# MCU.net
KiCad netlist of a schematic drawn in Altium Designer
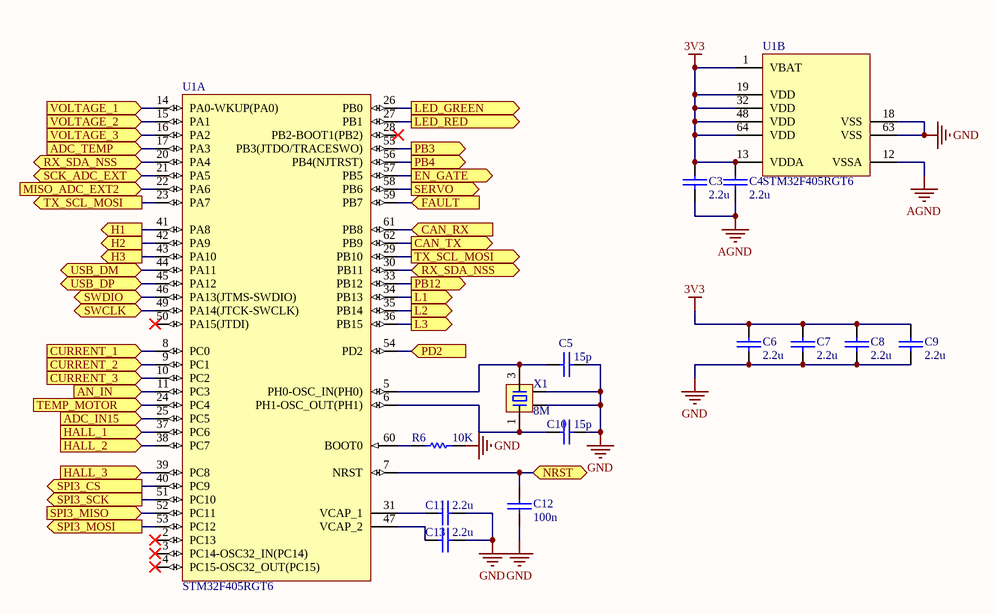
[diagram p0: MCU.SchDoc]

(export (version "E")
  (design (tool "Eeschema 10.0.6"))
  (components
    (comp (ref "C3")
      (value "2.2u")
      (footprint "0603C")
      (description "无极性电容")
      (libsource (lib "电容") (part "CAP"))
    )
    (comp (ref "C4")
      (value "2.2u")
      (footprint "0603C")
      (description "无极性电容")
      (libsource (lib "电容") (part "CAP"))
    )
    (comp (ref "C5")
      (value "15p")
      (footprint "0603C")
      (description "无极性电容")
      (libsource (lib "电容") (part "CAP"))
    )
    (comp (ref "C6")
      (value "2.2u")
      (footprint "0603C")
      (description "无极性电容")
      (libsource (lib "电容") (part "CAP"))
    )
    (comp (ref "C7")
      (value "2.2u")
      (footprint "0603C")
      (description "无极性电容")
      (libsource (lib "电容") (part "CAP"))
    )
    (comp (ref "C8")
      (value "2.2u")
      (footprint "0603C")
      (description "无极性电容")
      (libsource (lib "电容") (part "CAP"))
    )
    (comp (ref "C9")
      (value "2.2u")
      (footprint "0603C")
      (description "无极性电容")
      (libsource (lib "电容") (part "CAP"))
    )
    (comp (ref "C10")
      (value "15p")
      (footprint "0603C")
      (description "无极性电容")
      (libsource (lib "电容") (part "CAP"))
    )
    (comp (ref "C11")
      (value "2.2u")
      (footprint "0603C")
      (description "无极性电容")
      (libsource (lib "电容") (part "CAP"))
    )
    (comp (ref "C12")
      (value "100n")
      (footprint "0603C")
      (description "无极性电容")
      (libsource (lib "电容") (part "CAP"))
    )
    (comp (ref "C13")
      (value "2.2u")
      (footprint "0603C")
      (description "无极性电容")
      (libsource (lib "电容") (part "CAP"))
    )
    (comp (ref "R6") (value "10K") (footprint "0603R") (libsource (lib "电阻") (part "RES")))
    (comp (ref "U1")
      (value "STM32F405RGT6")
      (footprint "STM-LQFP64_N")
      (fields (field (name "MANUFACTURER") "STMicroelectronics"))
      (libsource (lib "Altium Content Vault") (part "MC-ARM-STM32F4X5-SQ64"))
    )
    (comp (ref "X1")
      (value "8M")
      (footprint "OSC 5032-4P")
      (description "4脚无源晶振")
      (libsource (lib "晶振") (part "XTAL-4P"))
    )
  )
  (nets
    (net (code "1") (name "/ADC_IN15") (class "Default")
      (node (ref "U1") (pin "25") (pinfunction "PC5_25") (pintype "bidirectional"))
    )
    (net (code "2") (name "/ADC_TEMP") (class "Default")
      (node (ref "U1") (pin "17") (pinfunction "PA3_17") (pintype "bidirectional"))
    )
    (net (code "3") (name "/AN_IN") (class "Default")
      (node (ref "U1") (pin "11") (pinfunction "PC3_11") (pintype "bidirectional"))
    )
    (net (code "4") (name "/CAN_RX") (class "Default")
      (node (ref "U1") (pin "61") (pinfunction "PB8_61") (pintype "bidirectional"))
    )
    (net (code "5") (name "/CAN_TX") (class "Default")
      (node (ref "U1") (pin "62") (pinfunction "PB9_62") (pintype "bidirectional"))
    )
    (net (code "6") (name "/CURRENT_1") (class "Default")
      (node (ref "U1") (pin "8") (pinfunction "PC0_8") (pintype "bidirectional"))
    )
    (net (code "7") (name "/CURRENT_2") (class "Default")
      (node (ref "U1") (pin "9") (pinfunction "PC1_9") (pintype "bidirectional"))
    )
    (net (code "8") (name "/CURRENT_3") (class "Default")
      (node (ref "U1") (pin "10") (pinfunction "PC2_10") (pintype "bidirectional"))
    )
    (net (code "9") (name "/EN_GATE") (class "Default")
      (node (ref "U1") (pin "57") (pinfunction "PB5_57") (pintype "bidirectional"))
    )
    (net (code "10") (name "/FAULT") (class "Default")
      (node (ref "U1") (pin "59") (pinfunction "PB7_59") (pintype "bidirectional"))
    )
    (net (code "11") (name "/H1") (class "Default")
      (node (ref "U1") (pin "41") (pinfunction "PA8_41") (pintype "bidirectional"))
    )
    (net (code "12") (name "/H2") (class "Default")
      (node (ref "U1") (pin "42") (pinfunction "PA9_42") (pintype "bidirectional"))
    )
    (net (code "13") (name "/H3") (class "Default")
      (node (ref "U1") (pin "43") (pinfunction "PA10_43") (pintype "bidirectional"))
    )
    (net (code "14") (name "/HALL_1") (class "Default")
      (node (ref "U1") (pin "37") (pinfunction "PC6_37") (pintype "bidirectional"))
    )
    (net (code "15") (name "/HALL_2") (class "Default")
      (node (ref "U1") (pin "38") (pinfunction "PC7_38") (pintype "bidirectional"))
    )
    (net (code "16") (name "/HALL_3") (class "Default")
      (node (ref "U1") (pin "39") (pinfunction "PC8_39") (pintype "bidirectional"))
    )
    (net (code "17") (name "/L1") (class "Default")
      (node (ref "U1") (pin "34") (pinfunction "PB13_34") (pintype "bidirectional"))
    )
    (net (code "18") (name "/L2") (class "Default")
      (node (ref "U1") (pin "35") (pinfunction "PB14_35") (pintype "bidirectional"))
    )
    (net (code "19") (name "/L3") (class "Default")
      (node (ref "U1") (pin "36") (pinfunction "PB15_36") (pintype "bidirectional"))
    )
    (net (code "20") (name "/LED_GREEN") (class "Default")
      (node (ref "U1") (pin "26") (pinfunction "PB0_26") (pintype "bidirectional"))
    )
    (net (code "21") (name "/LED_RED") (class "Default")
      (node (ref "U1") (pin "27") (pinfunction "PB1_27") (pintype "bidirectional"))
    )
    (net (code "22") (name "/MISO_ADC_EXT2") (class "Default")
      (node (ref "U1") (pin "22") (pinfunction "PA6_22") (pintype "bidirectional"))
    )
    (net (code "23") (name "/NRST") (class "Default")
      (node (ref "C12") (pin "1") (pinfunction "1_1") (pintype "passive"))
      (node (ref "U1") (pin "7") (pinfunction "NRST_7") (pintype "bidirectional"))
    )
    (net (code "24") (name "/PB3") (class "Default")
      (node (ref "U1") (pin "55") (pinfunction "PB3(JTDO/TRACESWO)_55") (pintype "bidirectional"))
    )
    (net (code "25") (name "/PB4") (class "Default")
      (node (ref "U1") (pin "56") (pinfunction "PB4(NJTRST)_56") (pintype "bidirectional"))
    )
    (net (code "26") (name "/PB12") (class "Default")
      (node (ref "U1") (pin "33") (pinfunction "PB12_33") (pintype "bidirectional"))
    )
    (net (code "27") (name "/PD2") (class "Default")
      (node (ref "U1") (pin "54") (pinfunction "PD2_54") (pintype "bidirectional"))
    )
    (net (code "28") (name "/RX_SDA_NSS") (class "Default")
      (node (ref "U1") (pin "20") (pinfunction "PA4_20") (pintype "bidirectional"))
      (node (ref "U1") (pin "30") (pinfunction "PB11_30") (pintype "bidirectional"))
    )
    (net (code "29") (name "/SCK_ADC_EXT") (class "Default")
      (node (ref "U1") (pin "21") (pinfunction "PA5_21") (pintype "bidirectional"))
    )
    (net (code "30") (name "/SERVO") (class "Default")
      (node (ref "U1") (pin "58") (pinfunction "PB6_58") (pintype "bidirectional"))
    )
    (net (code "31") (name "/SPI3_CS") (class "Default")
      (node (ref "U1") (pin "40") (pinfunction "PC9_40") (pintype "bidirectional"))
    )
    (net (code "32") (name "/SPI3_MISO") (class "Default")
      (node (ref "U1") (pin "52") (pinfunction "PC11_52") (pintype "bidirectional"))
    )
    (net (code "33") (name "/SPI3_MOSI") (class "Default")
      (node (ref "U1") (pin "53") (pinfunction "PC12_53") (pintype "bidirectional"))
    )
    (net (code "34") (name "/SPI3_SCK") (class "Default")
      (node (ref "U1") (pin "51") (pinfunction "PC10_51") (pintype "bidirectional"))
    )
    (net (code "35") (name "/SWCLK") (class "Default")
      (node (ref "U1") (pin "49") (pinfunction "PA14(JTCK-SWCLK)_49") (pintype "bidirectional"))
    )
    (net (code "36") (name "/SWDIO") (class "Default")
      (node (ref "U1") (pin "46") (pinfunction "PA13(JTMS-SWDIO)_46") (pintype "bidirectional"))
    )
    (net (code "37") (name "/TEMP_MOTOR") (class "Default")
      (node (ref "U1") (pin "24") (pinfunction "PC4_24") (pintype "bidirectional"))
    )
    (net (code "38") (name "/TX_SCL_MOSI") (class "Default")
      (node (ref "U1") (pin "23") (pinfunction "PA7_23") (pintype "bidirectional"))
      (node (ref "U1") (pin "29") (pinfunction "PB10_29") (pintype "bidirectional"))
    )
    (net (code "39") (name "/USB_DM") (class "Default")
      (node (ref "U1") (pin "44") (pinfunction "PA11_44") (pintype "bidirectional"))
    )
    (net (code "40") (name "/USB_DP") (class "Default")
      (node (ref "U1") (pin "45") (pinfunction "PA12_45") (pintype "bidirectional"))
    )
    (net (code "41") (name "/VOLTAGE_1") (class "Default")
      (node (ref "U1") (pin "14") (pinfunction "PA0-WKUP(PA0)_14") (pintype "bidirectional"))
    )
    (net (code "42") (name "/VOLTAGE_2") (class "Default")
      (node (ref "U1") (pin "15") (pinfunction "PA1_15") (pintype "bidirectional"))
    )
    (net (code "43") (name "/VOLTAGE_3") (class "Default")
      (node (ref "U1") (pin "16") (pinfunction "PA2_16") (pintype "bidirectional"))
    )
    (net (code "44") (name "3V3") (class "Default")
      (node (ref "C3") (pin "1") (pinfunction "1_1") (pintype "passive"))
      (node (ref "C4") (pin "1") (pinfunction "1_1") (pintype "passive"))
      (node (ref "C6") (pin "1") (pinfunction "1_1") (pintype "passive"))
      (node (ref "C7") (pin "1") (pinfunction "1_1") (pintype "passive"))
      (node (ref "C8") (pin "1") (pinfunction "1_1") (pintype "passive"))
      (node (ref "C9") (pin "1") (pinfunction "1_1") (pintype "passive"))
      (node (ref "U1") (pin "1") (pinfunction "VBAT_1") (pintype "power_in"))
      (node (ref "U1") (pin "13") (pinfunction "VDDA_13") (pintype "power_in"))
      (node (ref "U1") (pin "19") (pinfunction "VDD_19") (pintype "power_in"))
      (node (ref "U1") (pin "32") (pinfunction "VDD_32") (pintype "power_in"))
      (node (ref "U1") (pin "48") (pinfunction "VDD_48") (pintype "power_in"))
      (node (ref "U1") (pin "64") (pinfunction "VDD_64") (pintype "power_in"))
    )
    (net (code "45") (name "AGND") (class "Default")
      (node (ref "C3") (pin "2") (pinfunction "2_2") (pintype "passive"))
      (node (ref "C4") (pin "2") (pinfunction "2_2") (pintype "passive"))
      (node (ref "U1") (pin "12") (pinfunction "VSSA_12") (pintype "power_in"))
    )
    (net (code "46") (name "GND") (class "Default")
      (node (ref "C10") (pin "1") (pinfunction "1_1") (pintype "passive"))
      (node (ref "C11") (pin "1") (pinfunction "1_1") (pintype "passive"))
      (node (ref "C12") (pin "2") (pinfunction "2_2") (pintype "passive"))
      (node (ref "C13") (pin "1") (pinfunction "1_1") (pintype "passive"))
      (node (ref "C5") (pin "1") (pinfunction "1_1") (pintype "passive"))
      (node (ref "C6") (pin "2") (pinfunction "2_2") (pintype "passive"))
      (node (ref "C7") (pin "2") (pinfunction "2_2") (pintype "passive"))
      (node (ref "C8") (pin "2") (pinfunction "2_2") (pintype "passive"))
      (node (ref "C9") (pin "2") (pinfunction "2_2") (pintype "passive"))
      (node (ref "R6") (pin "2") (pinfunction "2_2") (pintype "passive"))
      (node (ref "U1") (pin "18") (pinfunction "VSS_18") (pintype "power_in"))
      (node (ref "U1") (pin "63") (pinfunction "VSS_63") (pintype "power_in"))
      (node (ref "X1") (pin "2") (pinfunction "2_2") (pintype "passive"))
      (node (ref "X1") (pin "4") (pinfunction "4_4") (pintype "passive"))
    )
    (net (code "47") (name "Net-(U1A-BOOT0)") (class "Default")
      (node (ref "R6") (pin "1") (pinfunction "1_1") (pintype "passive"))
      (node (ref "U1") (pin "60") (pinfunction "BOOT0_60") (pintype "input"))
    )
    (net (code "48") (name "Net-(U1A-PH0-OSC_IN(PH0))") (class "Default")
      (node (ref "C5") (pin "2") (pinfunction "2_2") (pintype "passive"))
      (node (ref "U1") (pin "5") (pinfunction "PH0-OSC_IN(PH0)_5") (pintype "bidirectional"))
      (node (ref "X1") (pin "3") (pinfunction "3_3") (pintype "passive"))
    )
    (net (code "49") (name "Net-(U1A-PH1-OSC_OUT(PH1))") (class "Default")
      (node (ref "C10") (pin "2") (pinfunction "2_2") (pintype "passive"))
      (node (ref "U1") (pin "6") (pinfunction "PH1-OSC_OUT(PH1)_6") (pintype "bidirectional"))
      (node (ref "X1") (pin "1") (pinfunction "1_1") (pintype "passive"))
    )
    (net (code "50") (name "Net-(U1A-VCAP_1)") (class "Default")
      (node (ref "C11") (pin "2") (pinfunction "2_2") (pintype "passive"))
      (node (ref "U1") (pin "31") (pinfunction "VCAP_1_31") (pintype "power_in"))
    )
    (net (code "51") (name "Net-(U1A-VCAP_2)") (class "Default")
      (node (ref "C13") (pin "2") (pinfunction "2_2") (pintype "passive"))
      (node (ref "U1") (pin "47") (pinfunction "VCAP_2_47") (pintype "power_in"))
    )
    (net (code "52") (name "unconnected-(U1A-PA15(JTDI)-Pad50)") (class "Default")
      (node (ref "U1") (pin "50") (pinfunction "PA15(JTDI)_50") (pintype "bidirectional+no_connect"))
    )
    (net (code "53") (name "unconnected-(U1A-PB2-BOOT1(PB2)-Pad28)") (class "Default")
      (node (ref "U1") (pin "28") (pinfunction "PB2-BOOT1(PB2)_28") (pintype "bidirectional+no_connect"))
    )
    (net (code "54") (name "unconnected-(U1A-PC13-Pad2)") (class "Default")
      (node (ref "U1") (pin "2") (pinfunction "PC13_2") (pintype "bidirectional+no_connect"))
    )
    (net (code "55") (name "unconnected-(U1A-PC14-OSC32_IN(PC14)-Pad3)") (class "Default")
      (node (ref "U1") (pin "3") (pinfunction "PC14-OSC32_IN(PC14)_3") (pintype "bidirectional+no_connect"))
    )
    (net (code "56") (name "unconnected-(U1A-PC15-OSC32_OUT(PC15)-Pad4)") (class "Default")
      (node (ref "U1") (pin "4") (pinfunction "PC15-OSC32_OUT(PC15)_4") (pintype "bidirectional+no_connect"))
    )
  )
)
